# SmartCard.net
KiCad netlist of a schematic drawn in Altium Designer
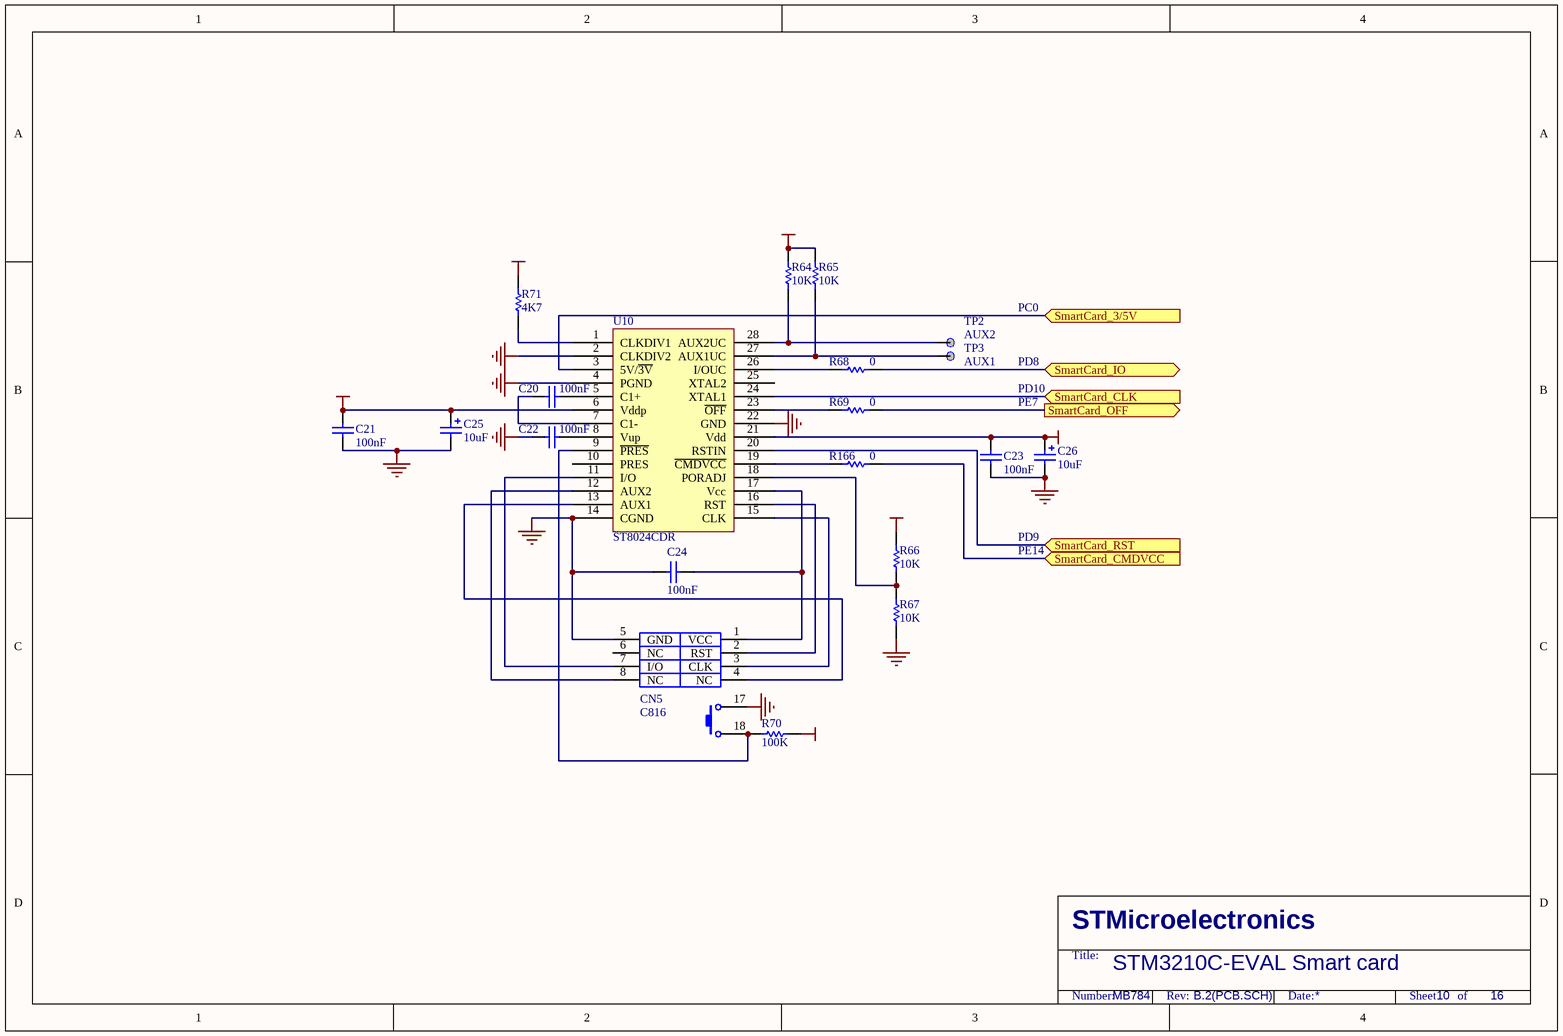
[diagram p0: SmartCard.SchDoc]

(export (version "E")
  (design (tool "Eeschema 10.0.6"))
  (components
    (comp (ref "C20")
      (value "100nF")
      (footprint "0603C")
      (description "Capacitor")
      (fields (field (name "PUBLISHER") "Altium Limited"))
      (libsource (lib "Miscellaneous Devices") (part "CAP"))
    )
    (comp (ref "C21")
      (value "100nF")
      (footprint "0603C")
      (description "Capacitor")
      (fields (field (name "PUBLISHER") "Altium Limited"))
      (libsource (lib "Miscellaneous Devices") (part "CAP"))
    )
    (comp (ref "C22")
      (value "100nF")
      (footprint "0603C")
      (description "Capacitor")
      (fields (field (name "PUBLISHER") "Altium Limited"))
      (libsource (lib "Miscellaneous Devices") (part "CAP"))
    )
    (comp (ref "C23")
      (value "100nF")
      (footprint "0603C")
      (description "Capacitor")
      (fields (field (name "PUBLISHER") "Altium Limited"))
      (libsource (lib "Miscellaneous Devices") (part "CAP"))
    )
    (comp (ref "C24")
      (value "100nF")
      (footprint "0603C")
      (description "Capacitor")
      (fields (field (name "PUBLISHER") "Altium Limited"))
      (libsource (lib "Miscellaneous Devices") (part "CAP"))
    )
    (comp (ref "C25")
      (value "10uF")
      (footprint "TAN-A")
      (description "Polarized Capacitor (Radial)")
      (fields (field (name "PUBLISHER") "Altium Limited"))
      (libsource (lib "Miscellaneous Devices") (part "Cap Pol1"))
    )
    (comp (ref "C26")
      (value "10uF")
      (footprint "TAN-A")
      (description "Polarized Capacitor (Radial)")
      (fields (field (name "PUBLISHER") "Altium Limited"))
      (libsource (lib "Miscellaneous Devices") (part "Cap Pol1"))
    )
    (comp (ref "CN5") (value "C816") (footprint "SAM(C816)") (libsource (lib "MB525") (part "Smart_card_CN")))
    (comp (ref "R64")
      (value "10K")
      (footprint "0603R")
      (description "Resistor")
      (fields (field (name "PUBLISHER") "Altium Limited"))
      (libsource (lib "Miscellaneous Devices") (part "Res1"))
    )
    (comp (ref "R65")
      (value "10K")
      (footprint "0603R")
      (description "Resistor")
      (fields (field (name "PUBLISHER") "Altium Limited"))
      (libsource (lib "Miscellaneous Devices") (part "Res1"))
    )
    (comp (ref "R66")
      (value "10K")
      (footprint "0603R")
      (description "Resistor")
      (fields (field (name "PUBLISHER") "Altium Limited"))
      (libsource (lib "Miscellaneous Devices") (part "Res1"))
    )
    (comp (ref "R67")
      (value "10K")
      (footprint "0603R")
      (description "Resistor")
      (fields (field (name "PUBLISHER") "Altium Limited"))
      (libsource (lib "Miscellaneous Devices") (part "Res1"))
    )
    (comp (ref "R68")
      (value "0")
      (footprint "0603R")
      (description "Resistor")
      (fields (field (name "PUBLISHER") "Altium Limited"))
      (libsource (lib "Miscellaneous Devices") (part "Res1"))
    )
    (comp (ref "R69")
      (value "0")
      (footprint "0603R")
      (description "Resistor")
      (fields (field (name "PUBLISHER") "Altium Limited"))
      (libsource (lib "Miscellaneous Devices") (part "Res1"))
    )
    (comp (ref "R70")
      (value "100K")
      (footprint "0603R")
      (description "Resistor")
      (fields (field (name "PUBLISHER") "Altium Limited"))
      (libsource (lib "Miscellaneous Devices") (part "Res1"))
    )
    (comp (ref "R71")
      (value "4K7")
      (footprint "0603R")
      (description "Resistor")
      (fields (field (name "PUBLISHER") "Altium Limited"))
      (libsource (lib "Miscellaneous Devices") (part "Res1"))
    )
    (comp (ref "R166")
      (value "0")
      (footprint "0603R")
      (description "Resistor")
      (fields (field (name "PUBLISHER") "Altium Limited"))
      (libsource (lib "Miscellaneous Devices") (part "Res1"))
    )
    (comp (ref "TP2") (value "AUX2") (footprint "TP") (libsource (lib "*") (part "TP")))
    (comp (ref "TP3") (value "AUX1") (footprint "TP") (libsource (lib "*") (part "TP")))
    (comp (ref "U10") (value "ST8024CDR") (footprint "SO28") (libsource (lib "MB525") (part "ST8024CTR")))
  )
  (nets
    (net (code "1") (name "+3V3") (class "Default")
      (node (ref "C23") (pin "1") (pinfunction "1_1") (pintype "passive"))
      (node (ref "C26") (pin "1") (pinfunction "1_1") (pintype "passive"))
      (node (ref "R64") (pin "1") (pinfunction "1_1") (pintype "passive"))
      (node (ref "R65") (pin "1") (pinfunction "1_1") (pintype "passive"))
      (node (ref "R66") (pin "1") (pinfunction "1_1") (pintype "passive"))
      (node (ref "R70") (pin "1") (pinfunction "1_1") (pintype "passive"))
      (node (ref "R71") (pin "1") (pinfunction "1_1") (pintype "passive"))
      (node (ref "U10") (pin "21") (pinfunction "Vdd_21") (pintype "passive"))
    )
    (net (code "2") (name "+5V") (class "Default")
      (node (ref "C21") (pin "1") (pinfunction "1_1") (pintype "passive"))
      (node (ref "C25") (pin "1") (pinfunction "1_1") (pintype "passive"))
      (node (ref "U10") (pin "6") (pinfunction "Vddp_6") (pintype "passive"))
    )
    (net (code "3") (name "/SmartCard_3{slash}5V") (class "Default")
      (node (ref "U10") (pin "3") (pinfunction "5V/~{3V}_3") (pintype "passive"))
    )
    (net (code "4") (name "/SmartCard_CLK") (class "Default")
      (node (ref "U10") (pin "24") (pinfunction "XTAL1_24") (pintype "passive"))
    )
    (net (code "5") (name "/SmartCard_CMDVCC") (class "Default")
      (node (ref "R166") (pin "1") (pinfunction "1_1") (pintype "passive"))
    )
    (net (code "6") (name "/SmartCard_IO") (class "Default")
      (node (ref "R68") (pin "2") (pinfunction "2_2") (pintype "passive"))
    )
    (net (code "7") (name "/SmartCard_OFF") (class "Default")
      (node (ref "R69") (pin "1") (pinfunction "1_1") (pintype "passive"))
    )
    (net (code "8") (name "/SmartCard_RST") (class "Default")
      (node (ref "U10") (pin "20") (pinfunction "RSTIN_20") (pintype "passive"))
    )
    (net (code "9") (name "GND") (class "Default")
      (node (ref "C21") (pin "2") (pinfunction "2_2") (pintype "passive"))
      (node (ref "C22") (pin "2") (pinfunction "2_2") (pintype "passive"))
      (node (ref "C23") (pin "2") (pinfunction "2_2") (pintype "passive"))
      (node (ref "C24") (pin "1") (pinfunction "1_1") (pintype "passive"))
      (node (ref "C25") (pin "2") (pinfunction "2_2") (pintype "passive"))
      (node (ref "C26") (pin "2") (pinfunction "2_2") (pintype "passive"))
      (node (ref "CN5") (pin "17") (pintype "passive"))
      (node (ref "CN5") (pin "5") (pinfunction "GND_5") (pintype "passive"))
      (node (ref "R67") (pin "2") (pinfunction "2_2") (pintype "passive"))
      (node (ref "U10") (pin "14") (pinfunction "CGND_14") (pintype "passive"))
      (node (ref "U10") (pin "2") (pinfunction "CLKDIV2_2") (pintype "passive"))
      (node (ref "U10") (pin "22") (pinfunction "GND_22") (pintype "passive"))
      (node (ref "U10") (pin "4") (pinfunction "PGND_4") (pintype "passive"))
    )
    (net (code "10") (name "Net-(CN5-CLK)") (class "Default")
      (node (ref "CN5") (pin "3") (pinfunction "CLK_3") (pintype "passive"))
      (node (ref "U10") (pin "15") (pinfunction "CLK_15") (pintype "passive"))
    )
    (net (code "11") (name "Net-(CN5-I{slash}O)") (class "Default")
      (node (ref "CN5") (pin "7") (pinfunction "I/O_7") (pintype "passive"))
      (node (ref "U10") (pin "11") (pinfunction "I/O_11") (pintype "passive"))
    )
    (net (code "12") (name "Net-(CN5-RST)") (class "Default")
      (node (ref "CN5") (pin "2") (pinfunction "RST_2") (pintype "passive"))
      (node (ref "U10") (pin "16") (pinfunction "RST_16") (pintype "passive"))
    )
    (net (code "13") (name "Net-(CN5-VCC)") (class "Default")
      (node (ref "C24") (pin "2") (pinfunction "2_2") (pintype "passive"))
      (node (ref "CN5") (pin "1") (pinfunction "VCC_1") (pintype "passive"))
      (node (ref "U10") (pin "17") (pinfunction "Vcc_17") (pintype "passive"))
    )
    (net (code "14") (name "Net-(U10-AUX1)") (class "Default")
      (node (ref "CN5") (pin "4") (pinfunction "NC_4") (pintype "passive"))
      (node (ref "U10") (pin "13") (pinfunction "AUX1_13") (pintype "passive"))
    )
    (net (code "15") (name "Net-(U10-AUX1UC)") (class "Default")
      (node (ref "R65") (pin "2") (pinfunction "2_2") (pintype "passive"))
      (node (ref "TP3") (pin "1") (pinfunction "1_1") (pintype "passive"))
      (node (ref "U10") (pin "27") (pinfunction "AUX1UC_27") (pintype "passive"))
    )
    (net (code "16") (name "Net-(U10-AUX2)") (class "Default")
      (node (ref "CN5") (pin "8") (pinfunction "NC_8") (pintype "passive"))
      (node (ref "U10") (pin "12") (pinfunction "AUX2_12") (pintype "passive"))
    )
    (net (code "17") (name "Net-(U10-AUX2UC)") (class "Default")
      (node (ref "R64") (pin "2") (pinfunction "2_2") (pintype "passive"))
      (node (ref "TP2") (pin "1") (pinfunction "1_1") (pintype "passive"))
      (node (ref "U10") (pin "28") (pinfunction "AUX2UC_28") (pintype "passive"))
    )
    (net (code "18") (name "Net-(U10-C1+)") (class "Default")
      (node (ref "C20") (pin "2") (pinfunction "2_2") (pintype "passive"))
      (node (ref "U10") (pin "5") (pinfunction "C1+_5") (pintype "passive"))
    )
    (net (code "19") (name "Net-(U10-C1-)") (class "Default")
      (node (ref "C20") (pin "1") (pinfunction "1_1") (pintype "passive"))
      (node (ref "U10") (pin "7") (pinfunction "C1-_7") (pintype "passive"))
    )
    (net (code "20") (name "Net-(U10-CLKDIV1)") (class "Default")
      (node (ref "R71") (pin "2") (pinfunction "2_2") (pintype "passive"))
      (node (ref "U10") (pin "1") (pinfunction "CLKDIV1_1") (pintype "passive"))
    )
    (net (code "21") (name "Net-(U10-I{slash}OUC)") (class "Default")
      (node (ref "R68") (pin "1") (pinfunction "1_1") (pintype "passive"))
      (node (ref "U10") (pin "26") (pinfunction "I/OUC_26") (pintype "passive"))
    )
    (net (code "22") (name "Net-(U10-PORADJ)") (class "Default")
      (node (ref "R66") (pin "2") (pinfunction "2_2") (pintype "passive"))
      (node (ref "R67") (pin "1") (pinfunction "1_1") (pintype "passive"))
      (node (ref "U10") (pin "18") (pinfunction "PORADJ_18") (pintype "passive"))
    )
    (net (code "23") (name "Net-(U10-Vup)") (class "Default")
      (node (ref "C22") (pin "1") (pinfunction "1_1") (pintype "passive"))
      (node (ref "U10") (pin "8") (pinfunction "Vup_8") (pintype "passive"))
    )
    (net (code "24") (name "Net-(U10-~{CMDVCC})") (class "Default")
      (node (ref "R166") (pin "2") (pinfunction "2_2") (pintype "passive"))
      (node (ref "U10") (pin "19") (pinfunction "~{CMDVCC}_19") (pintype "passive"))
    )
    (net (code "25") (name "Net-(U10-~{OFF})") (class "Default")
      (node (ref "R69") (pin "2") (pinfunction "2_2") (pintype "passive"))
      (node (ref "U10") (pin "23") (pinfunction "~{OFF}_23") (pintype "passive"))
    )
    (net (code "26") (name "Net-(U10-~{PRES})") (class "Default")
      (node (ref "CN5") (pin "18") (pintype "passive"))
      (node (ref "R70") (pin "2") (pinfunction "2_2") (pintype "passive"))
      (node (ref "U10") (pin "9") (pinfunction "~{PRES}_9") (pintype "passive"))
    )
    (net (code "27") (name "unconnected-(CN5-NC-Pad6)") (class "Default")
      (node (ref "CN5") (pin "6") (pinfunction "NC_6") (pintype "passive"))
    )
    (net (code "28") (name "unconnected-(U10-PRES-Pad10)") (class "Default")
      (node (ref "U10") (pin "10") (pinfunction "PRES_10") (pintype "passive"))
    )
    (net (code "29") (name "unconnected-(U10-XTAL2-Pad25)") (class "Default")
      (node (ref "U10") (pin "25") (pinfunction "XTAL2_25") (pintype "passive"))
    )
  )
)
